# SunS_Decoupler.net
KiCad netlist of a schematic drawn in Altium Designer
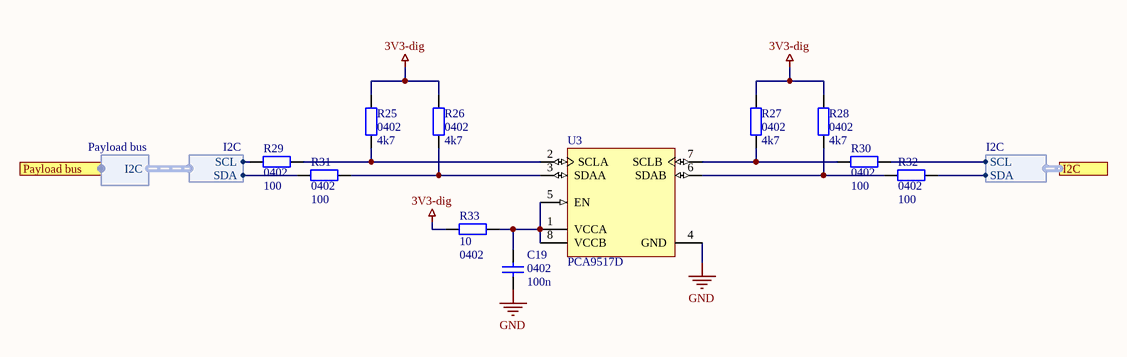
[diagram p0: SunS_Decoupler.SchDoc]

(export (version "E")
  (design (tool "Eeschema 10.0.6"))
  (components
    (comp (ref "C19")
      (value "0402")
      (footprint "SMD_Capacitor_0402")
      (description "Capacitor")
      (fields (field (name "ALTIUM_VALUE") "100n") (field (name "PUBLISHER") "Altium Limited"))
      (libsource (lib "Miscellaneous Devices") (part "Cap"))
    )
    (comp (ref "R25")
      (value "0402")
      (footprint "SMD_Resistor_0402")
      (description "Resistor")
      (fields (field (name "ALTIUM_VALUE") "4k7") (field (name "PUBLISHER") "Altium Limited"))
      (libsource (lib "Miscellaneous Devices") (part "Res2"))
    )
    (comp (ref "R26")
      (value "0402")
      (footprint "SMD_Resistor_0402")
      (description "Resistor")
      (fields (field (name "ALTIUM_VALUE") "4k7") (field (name "PUBLISHER") "Altium Limited"))
      (libsource (lib "Miscellaneous Devices") (part "Res2"))
    )
    (comp (ref "R27")
      (value "0402")
      (footprint "SMD_Resistor_0402")
      (description "Resistor")
      (fields (field (name "ALTIUM_VALUE") "4k7") (field (name "PUBLISHER") "Altium Limited"))
      (libsource (lib "Miscellaneous Devices") (part "Res2"))
    )
    (comp (ref "R28")
      (value "0402")
      (footprint "SMD_Resistor_0402")
      (description "Resistor")
      (fields (field (name "ALTIUM_VALUE") "4k7") (field (name "PUBLISHER") "Altium Limited"))
      (libsource (lib "Miscellaneous Devices") (part "Res2"))
    )
    (comp (ref "R29")
      (value "0402")
      (footprint "SMD_Resistor_0402")
      (description "Resistor")
      (fields (field (name "ALTIUM_VALUE") "100") (field (name "PUBLISHER") "Altium Limited"))
      (libsource (lib "") (part "Res2_1"))
    )
    (comp (ref "R30")
      (value "0402")
      (footprint "SMD_Resistor_0402")
      (description "Resistor")
      (fields (field (name "ALTIUM_VALUE") "100") (field (name "PUBLISHER") "Altium Limited"))
      (libsource (lib "") (part "Res2_1"))
    )
    (comp (ref "R31")
      (value "0402")
      (footprint "SMD_Resistor_0402")
      (description "Resistor")
      (fields (field (name "ALTIUM_VALUE") "100") (field (name "PUBLISHER") "Altium Limited"))
      (libsource (lib "") (part "Res2_1"))
    )
    (comp (ref "R32")
      (value "0402")
      (footprint "SMD_Resistor_0402")
      (description "Resistor")
      (fields (field (name "ALTIUM_VALUE") "100") (field (name "PUBLISHER") "Altium Limited"))
      (libsource (lib "") (part "Res2_1"))
    )
    (comp (ref "R33")
      (value "0402")
      (footprint "SMD_Resistor_0402")
      (description "Resistor")
      (fields (field (name "ALTIUM_VALUE") "10") (field (name "PUBLISHER") "Altium Limited"))
      (libsource (lib "") (part "Res2_1"))
    )
    (comp (ref "U3")
      (value "PCA9517D")
      (footprint "D8_N")
      (fields (field (name "MANUFACTURER") "Texas Instruments"))
      (libsource (lib "Interface_I2C") (part "PCA9517D"))
    )
  )
  (nets
    (net (code "7") (name "3V3-dig") (class "Default")
      (node (ref "R25") (pin "2") (pinfunction "2_2") (pintype "passive"))
      (node (ref "R26") (pin "2") (pinfunction "2_2") (pintype "passive"))
      (node (ref "R27") (pin "2") (pinfunction "2_2") (pintype "passive"))
      (node (ref "R28") (pin "2") (pinfunction "2_2") (pintype "passive"))
      (node (ref "R33") (pin "2") (pinfunction "2_2") (pintype "passive"))
    )
    (net (code "8") (name "GND") (class "Default")
      (node (ref "C19") (pin "1") (pinfunction "1_1") (pintype "passive"))
      (node (ref "U3") (pin "4") (pinfunction "GND_4") (pintype "power_in"))
    )
    (net (code "9") (name "Net-(U3-EN)") (class "Default")
      (node (ref "C19") (pin "2") (pinfunction "2_2") (pintype "passive"))
      (node (ref "R33") (pin "1") (pinfunction "1_1") (pintype "passive"))
      (node (ref "U3") (pin "1") (pinfunction "VCCA_1") (pintype "power_in"))
      (node (ref "U3") (pin "5") (pinfunction "EN_5") (pintype "input"))
      (node (ref "U3") (pin "8") (pinfunction "VCCB_8") (pintype "power_in"))
    )
    (net (code "10") (name "Net-(U3-SCLA)") (class "Default")
      (node (ref "R25") (pin "1") (pinfunction "1_1") (pintype "passive"))
      (node (ref "R29") (pin "1") (pinfunction "1_1") (pintype "passive"))
      (node (ref "U3") (pin "2") (pinfunction "SCLA_2") (pintype "bidirectional"))
    )
    (net (code "11") (name "Net-(U3-SCLB)") (class "Default")
      (node (ref "R27") (pin "1") (pinfunction "1_1") (pintype "passive"))
      (node (ref "R30") (pin "2") (pinfunction "2_2") (pintype "passive"))
      (node (ref "U3") (pin "7") (pinfunction "SCLB_7") (pintype "bidirectional"))
    )
    (net (code "12") (name "Net-(U3-SDAA)") (class "Default")
      (node (ref "R26") (pin "1") (pinfunction "1_1") (pintype "passive"))
      (node (ref "R31") (pin "1") (pinfunction "1_1") (pintype "passive"))
      (node (ref "U3") (pin "3") (pinfunction "SDAA_3") (pintype "bidirectional"))
    )
    (net (code "13") (name "Net-(U3-SDAB)") (class "Default")
      (node (ref "R28") (pin "1") (pinfunction "1_1") (pintype "passive"))
      (node (ref "R32") (pin "2") (pinfunction "2_2") (pintype "passive"))
      (node (ref "U3") (pin "6") (pinfunction "SDAB_6") (pintype "bidirectional"))
    )
    (net (code "14") (name "unconnected-(R29-Pad2)") (class "Default")
      (node (ref "R29") (pin "2") (pinfunction "2_2") (pintype "passive"))
    )
    (net (code "15") (name "unconnected-(R30-Pad1)") (class "Default")
      (node (ref "R30") (pin "1") (pinfunction "1_1") (pintype "passive"))
    )
    (net (code "16") (name "unconnected-(R31-Pad2)") (class "Default")
      (node (ref "R31") (pin "2") (pinfunction "2_2") (pintype "passive"))
    )
    (net (code "17") (name "unconnected-(R32-Pad1)") (class "Default")
      (node (ref "R32") (pin "1") (pinfunction "1_1") (pintype "passive"))
    )
  )
)
